# AxionAdapter.net
KiCad netlist of a schematic drawn in EAGLE
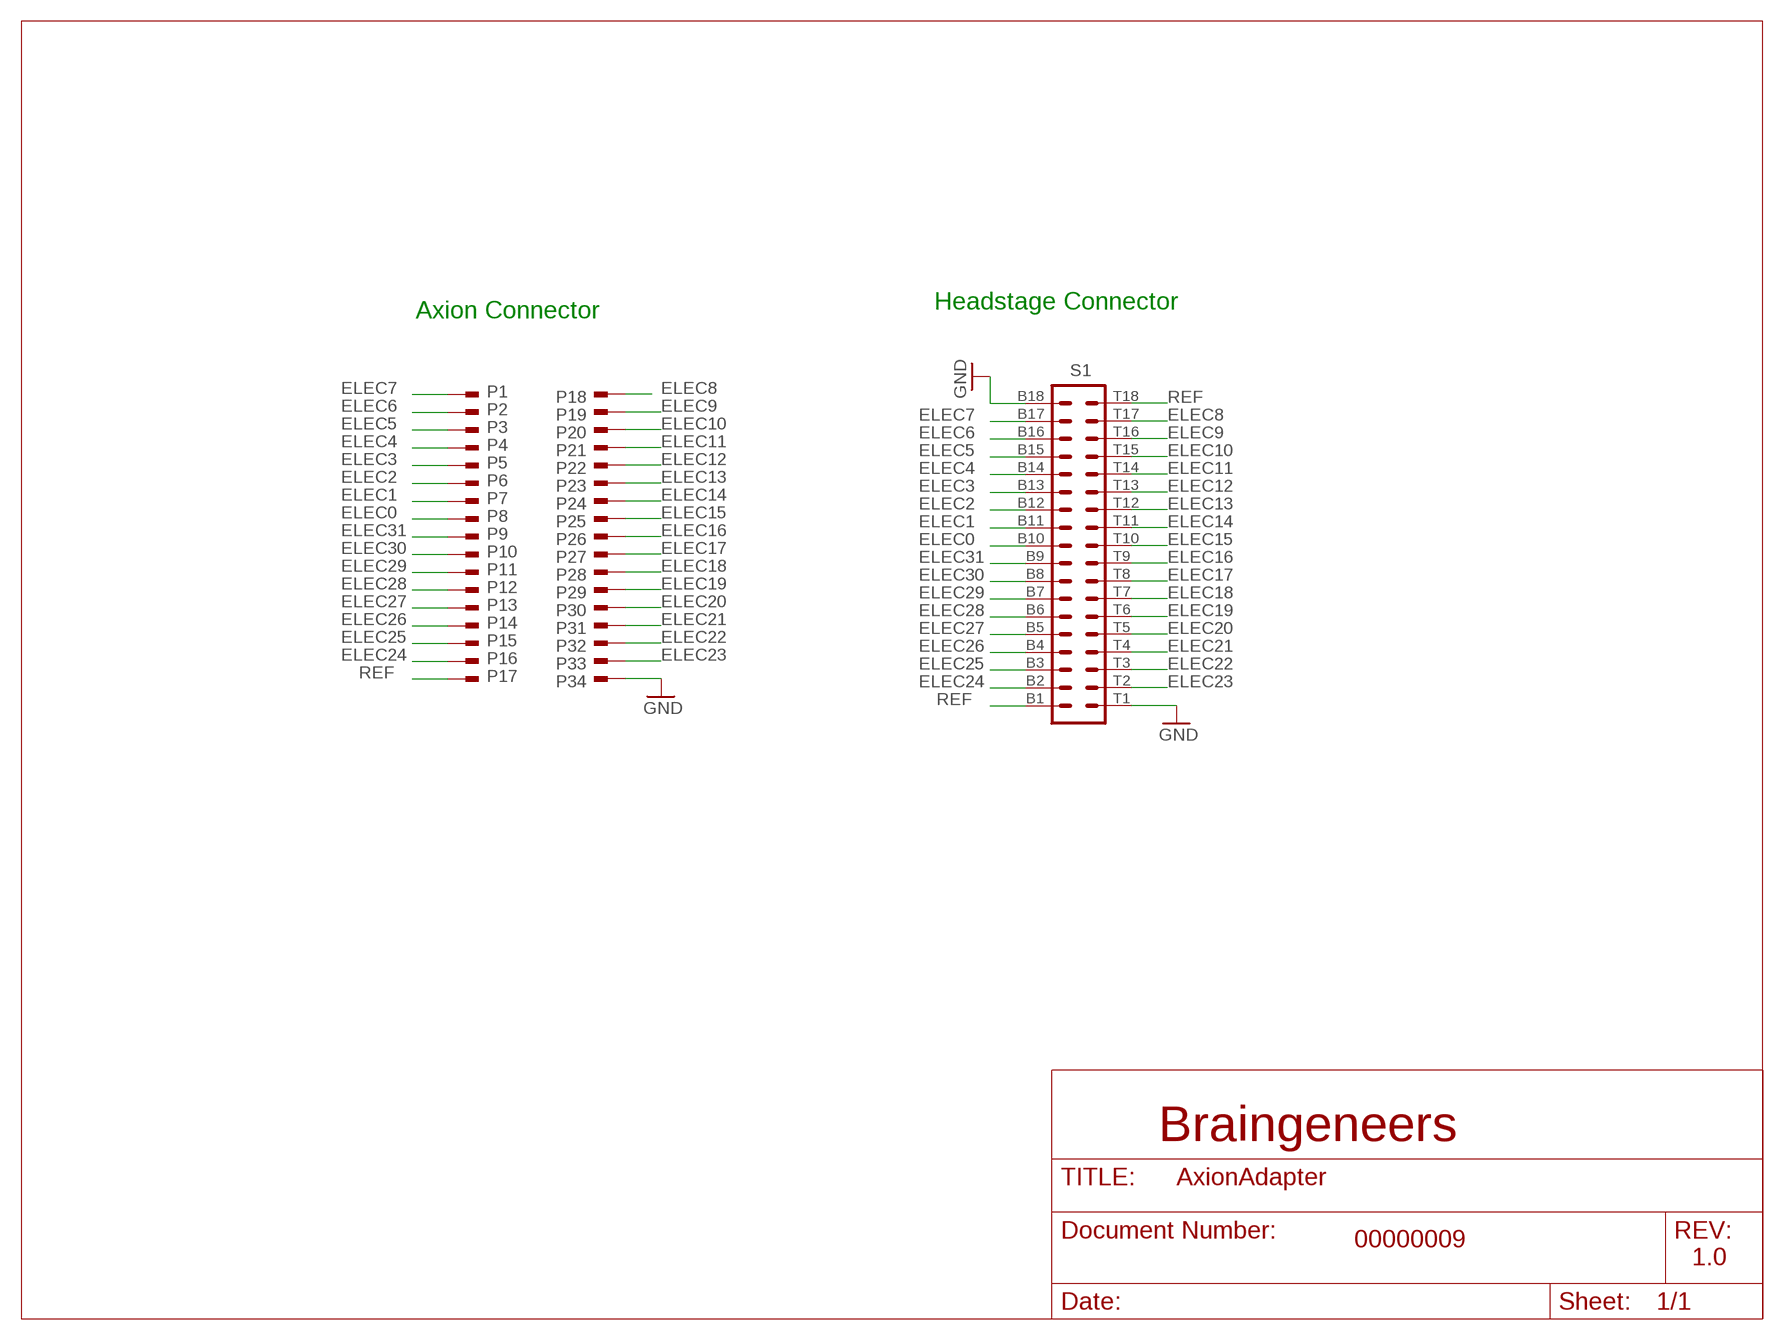
[diagram p0: schematic, sheet 1]

(export (version "E")
  (design (tool "Eeschema 10.0.6"))
  (components
    (comp (ref "P1")
      (value "2336713-2_TE")
      (footprint "eagle-import:2336713-2_TE")
      (libsource (lib "eagle-import") (part "2336713-2_TE"))
    )
    (comp (ref "P2")
      (value "2336713-2_TE")
      (footprint "eagle-import:2336713-2_TE")
      (libsource (lib "eagle-import") (part "2336713-2_TE"))
    )
    (comp (ref "P3")
      (value "2336713-2_TE")
      (footprint "eagle-import:2336713-2_TE")
      (libsource (lib "eagle-import") (part "2336713-2_TE"))
    )
    (comp (ref "P4")
      (value "2336713-2_TE")
      (footprint "eagle-import:2336713-2_TE")
      (libsource (lib "eagle-import") (part "2336713-2_TE"))
    )
    (comp (ref "P5")
      (value "2336713-2_TE")
      (footprint "eagle-import:2336713-2_TE")
      (libsource (lib "eagle-import") (part "2336713-2_TE"))
    )
    (comp (ref "P6")
      (value "2336713-2_TE")
      (footprint "eagle-import:2336713-2_TE")
      (libsource (lib "eagle-import") (part "2336713-2_TE"))
    )
    (comp (ref "P7")
      (value "2336713-2_TE")
      (footprint "eagle-import:2336713-2_TE")
      (libsource (lib "eagle-import") (part "2336713-2_TE"))
    )
    (comp (ref "P8")
      (value "2336713-2_TE")
      (footprint "eagle-import:2336713-2_TE")
      (libsource (lib "eagle-import") (part "2336713-2_TE"))
    )
    (comp (ref "P9")
      (value "2336713-2_TE")
      (footprint "eagle-import:2336713-2_TE")
      (libsource (lib "eagle-import") (part "2336713-2_TE"))
    )
    (comp (ref "P10")
      (value "2336713-2_TE")
      (footprint "eagle-import:2336713-2_TE")
      (libsource (lib "eagle-import") (part "2336713-2_TE"))
    )
    (comp (ref "P11")
      (value "2336713-2_TE")
      (footprint "eagle-import:2336713-2_TE")
      (libsource (lib "eagle-import") (part "2336713-2_TE"))
    )
    (comp (ref "P12")
      (value "2336713-2_TE")
      (footprint "eagle-import:2336713-2_TE")
      (libsource (lib "eagle-import") (part "2336713-2_TE"))
    )
    (comp (ref "P13")
      (value "2336713-2_TE")
      (footprint "eagle-import:2336713-2_TE")
      (libsource (lib "eagle-import") (part "2336713-2_TE"))
    )
    (comp (ref "P14")
      (value "2336713-2_TE")
      (footprint "eagle-import:2336713-2_TE")
      (libsource (lib "eagle-import") (part "2336713-2_TE"))
    )
    (comp (ref "P15")
      (value "2336713-2_TE")
      (footprint "eagle-import:2336713-2_TE")
      (libsource (lib "eagle-import") (part "2336713-2_TE"))
    )
    (comp (ref "P16")
      (value "2336713-2_TE")
      (footprint "eagle-import:2336713-2_TE")
      (libsource (lib "eagle-import") (part "2336713-2_TE"))
    )
    (comp (ref "P17")
      (value "2336713-2_TE")
      (footprint "eagle-import:2336713-2_TE")
      (libsource (lib "eagle-import") (part "2336713-2_TE"))
    )
    (comp (ref "P18")
      (value "2336713-2_TE")
      (footprint "eagle-import:2336713-2_TE")
      (libsource (lib "eagle-import") (part "2336713-2_TE"))
    )
    (comp (ref "P19")
      (value "2336713-2_TE")
      (footprint "eagle-import:2336713-2_TE")
      (libsource (lib "eagle-import") (part "2336713-2_TE"))
    )
    (comp (ref "P20")
      (value "2336713-2_TE")
      (footprint "eagle-import:2336713-2_TE")
      (libsource (lib "eagle-import") (part "2336713-2_TE"))
    )
    (comp (ref "P21")
      (value "2336713-2_TE")
      (footprint "eagle-import:2336713-2_TE")
      (libsource (lib "eagle-import") (part "2336713-2_TE"))
    )
    (comp (ref "P22")
      (value "2336713-2_TE")
      (footprint "eagle-import:2336713-2_TE")
      (libsource (lib "eagle-import") (part "2336713-2_TE"))
    )
    (comp (ref "P23")
      (value "2336713-2_TE")
      (footprint "eagle-import:2336713-2_TE")
      (libsource (lib "eagle-import") (part "2336713-2_TE"))
    )
    (comp (ref "P24")
      (value "2336713-2_TE")
      (footprint "eagle-import:2336713-2_TE")
      (libsource (lib "eagle-import") (part "2336713-2_TE"))
    )
    (comp (ref "P25")
      (value "2336713-2_TE")
      (footprint "eagle-import:2336713-2_TE")
      (libsource (lib "eagle-import") (part "2336713-2_TE"))
    )
    (comp (ref "P26")
      (value "2336713-2_TE")
      (footprint "eagle-import:2336713-2_TE")
      (libsource (lib "eagle-import") (part "2336713-2_TE"))
    )
    (comp (ref "P27")
      (value "2336713-2_TE")
      (footprint "eagle-import:2336713-2_TE")
      (libsource (lib "eagle-import") (part "2336713-2_TE"))
    )
    (comp (ref "P28")
      (value "2336713-2_TE")
      (footprint "eagle-import:2336713-2_TE")
      (libsource (lib "eagle-import") (part "2336713-2_TE"))
    )
    (comp (ref "P29")
      (value "2336713-2_TE")
      (footprint "eagle-import:2336713-2_TE")
      (libsource (lib "eagle-import") (part "2336713-2_TE"))
    )
    (comp (ref "P30")
      (value "2336713-2_TE")
      (footprint "eagle-import:2336713-2_TE")
      (libsource (lib "eagle-import") (part "2336713-2_TE"))
    )
    (comp (ref "P31")
      (value "2336713-2_TE")
      (footprint "eagle-import:2336713-2_TE")
      (libsource (lib "eagle-import") (part "2336713-2_TE"))
    )
    (comp (ref "P32")
      (value "2336713-2_TE")
      (footprint "eagle-import:2336713-2_TE")
      (libsource (lib "eagle-import") (part "2336713-2_TE"))
    )
    (comp (ref "P33")
      (value "2336713-2_TE")
      (footprint "eagle-import:2336713-2_TE")
      (libsource (lib "eagle-import") (part "2336713-2_TE"))
    )
    (comp (ref "P34")
      (value "2336713-2_TE")
      (footprint "eagle-import:2336713-2_TE")
      (libsource (lib "eagle-import") (part "2336713-2_TE"))
    )
    (comp (ref "S1")
      (value "OMNETICS_A79024")
      (footprint "eagle-import:OMNETICS_A79024")
      (libsource (lib "eagle-import") (part "OMNETICS_A79024"))
    )
  )
  (nets
    (net (code "1") (name "/ELEC0") (class "Default")
      (node (ref "P8") (pin "P$1") (pinfunction "1_P$1") (pintype "passive"))
      (node (ref "P8") (pin "P$2") (pinfunction "1_P$2") (pintype "passive"))
      (node (ref "S1") (pin "B10") (pinfunction "B10_B10") (pintype "passive"))
    )
    (net (code "2") (name "/ELEC1") (class "Default")
      (node (ref "P7") (pin "P$1") (pinfunction "1_P$1") (pintype "passive"))
      (node (ref "P7") (pin "P$2") (pinfunction "1_P$2") (pintype "passive"))
      (node (ref "S1") (pin "B11") (pinfunction "B11_B11") (pintype "passive"))
    )
    (net (code "3") (name "/ELEC2") (class "Default")
      (node (ref "P6") (pin "P$1") (pinfunction "1_P$1") (pintype "passive"))
      (node (ref "P6") (pin "P$2") (pinfunction "1_P$2") (pintype "passive"))
      (node (ref "S1") (pin "B12") (pinfunction "B12_B12") (pintype "passive"))
    )
    (net (code "4") (name "/ELEC3") (class "Default")
      (node (ref "P5") (pin "P$1") (pinfunction "1_P$1") (pintype "passive"))
      (node (ref "P5") (pin "P$2") (pinfunction "1_P$2") (pintype "passive"))
      (node (ref "S1") (pin "B13") (pinfunction "B13_B13") (pintype "passive"))
    )
    (net (code "5") (name "/ELEC4") (class "Default")
      (node (ref "P4") (pin "P$1") (pinfunction "1_P$1") (pintype "passive"))
      (node (ref "P4") (pin "P$2") (pinfunction "1_P$2") (pintype "passive"))
      (node (ref "S1") (pin "B14") (pinfunction "B14_B14") (pintype "passive"))
    )
    (net (code "6") (name "/ELEC5") (class "Default")
      (node (ref "P3") (pin "P$1") (pinfunction "1_P$1") (pintype "passive"))
      (node (ref "P3") (pin "P$2") (pinfunction "1_P$2") (pintype "passive"))
      (node (ref "S1") (pin "B15") (pinfunction "B15_B15") (pintype "passive"))
    )
    (net (code "7") (name "/ELEC6") (class "Default")
      (node (ref "P2") (pin "P$1") (pinfunction "1_P$1") (pintype "passive"))
      (node (ref "P2") (pin "P$2") (pinfunction "1_P$2") (pintype "passive"))
      (node (ref "S1") (pin "B16") (pinfunction "B16_B16") (pintype "passive"))
    )
    (net (code "8") (name "/ELEC7") (class "Default")
      (node (ref "P1") (pin "P$1") (pinfunction "1_P$1") (pintype "passive"))
      (node (ref "P1") (pin "P$2") (pinfunction "1_P$2") (pintype "passive"))
      (node (ref "S1") (pin "B17") (pinfunction "B17_B17") (pintype "passive"))
    )
    (net (code "9") (name "/ELEC8") (class "Default")
      (node (ref "P18") (pin "P$1") (pinfunction "1_P$1") (pintype "passive"))
      (node (ref "P18") (pin "P$2") (pinfunction "1_P$2") (pintype "passive"))
      (node (ref "S1") (pin "T17") (pinfunction "T17_T17") (pintype "passive"))
    )
    (net (code "10") (name "/ELEC9") (class "Default")
      (node (ref "P19") (pin "P$1") (pinfunction "1_P$1") (pintype "passive"))
      (node (ref "P19") (pin "P$2") (pinfunction "1_P$2") (pintype "passive"))
      (node (ref "S1") (pin "T16") (pinfunction "T16_T16") (pintype "passive"))
    )
    (net (code "11") (name "/ELEC10") (class "Default")
      (node (ref "P20") (pin "P$1") (pinfunction "1_P$1") (pintype "passive"))
      (node (ref "P20") (pin "P$2") (pinfunction "1_P$2") (pintype "passive"))
      (node (ref "S1") (pin "T15") (pinfunction "T15_T15") (pintype "passive"))
    )
    (net (code "12") (name "/ELEC11") (class "Default")
      (node (ref "P21") (pin "P$1") (pinfunction "1_P$1") (pintype "passive"))
      (node (ref "P21") (pin "P$2") (pinfunction "1_P$2") (pintype "passive"))
      (node (ref "S1") (pin "T14") (pinfunction "T14_T14") (pintype "passive"))
    )
    (net (code "13") (name "/ELEC12") (class "Default")
      (node (ref "P22") (pin "P$1") (pinfunction "1_P$1") (pintype "passive"))
      (node (ref "P22") (pin "P$2") (pinfunction "1_P$2") (pintype "passive"))
      (node (ref "S1") (pin "T13") (pinfunction "T13_T13") (pintype "passive"))
    )
    (net (code "14") (name "/ELEC13") (class "Default")
      (node (ref "P23") (pin "P$1") (pinfunction "1_P$1") (pintype "passive"))
      (node (ref "P23") (pin "P$2") (pinfunction "1_P$2") (pintype "passive"))
      (node (ref "S1") (pin "T12") (pinfunction "T12_T12") (pintype "passive"))
    )
    (net (code "15") (name "/ELEC14") (class "Default")
      (node (ref "P24") (pin "P$1") (pinfunction "1_P$1") (pintype "passive"))
      (node (ref "P24") (pin "P$2") (pinfunction "1_P$2") (pintype "passive"))
      (node (ref "S1") (pin "T11") (pinfunction "T11_T11") (pintype "passive"))
    )
    (net (code "16") (name "/ELEC15") (class "Default")
      (node (ref "P25") (pin "P$1") (pinfunction "1_P$1") (pintype "passive"))
      (node (ref "P25") (pin "P$2") (pinfunction "1_P$2") (pintype "passive"))
      (node (ref "S1") (pin "T10") (pinfunction "T10_T10") (pintype "passive"))
    )
    (net (code "17") (name "/ELEC16") (class "Default")
      (node (ref "P26") (pin "P$1") (pinfunction "1_P$1") (pintype "passive"))
      (node (ref "P26") (pin "P$2") (pinfunction "1_P$2") (pintype "passive"))
      (node (ref "S1") (pin "T9") (pinfunction "T9_T9") (pintype "passive"))
    )
    (net (code "18") (name "/ELEC17") (class "Default")
      (node (ref "P27") (pin "P$1") (pinfunction "1_P$1") (pintype "passive"))
      (node (ref "P27") (pin "P$2") (pinfunction "1_P$2") (pintype "passive"))
      (node (ref "S1") (pin "T8") (pinfunction "T8_T8") (pintype "passive"))
    )
    (net (code "19") (name "/ELEC18") (class "Default")
      (node (ref "P28") (pin "P$1") (pinfunction "1_P$1") (pintype "passive"))
      (node (ref "P28") (pin "P$2") (pinfunction "1_P$2") (pintype "passive"))
      (node (ref "S1") (pin "T7") (pinfunction "T7_T7") (pintype "passive"))
    )
    (net (code "20") (name "/ELEC19") (class "Default")
      (node (ref "P29") (pin "P$1") (pinfunction "1_P$1") (pintype "passive"))
      (node (ref "P29") (pin "P$2") (pinfunction "1_P$2") (pintype "passive"))
      (node (ref "S1") (pin "T6") (pinfunction "T6_T6") (pintype "passive"))
    )
    (net (code "21") (name "/ELEC20") (class "Default")
      (node (ref "P30") (pin "P$1") (pinfunction "1_P$1") (pintype "passive"))
      (node (ref "P30") (pin "P$2") (pinfunction "1_P$2") (pintype "passive"))
      (node (ref "S1") (pin "T5") (pinfunction "T5_T5") (pintype "passive"))
    )
    (net (code "22") (name "/ELEC21") (class "Default")
      (node (ref "P31") (pin "P$1") (pinfunction "1_P$1") (pintype "passive"))
      (node (ref "P31") (pin "P$2") (pinfunction "1_P$2") (pintype "passive"))
      (node (ref "S1") (pin "T4") (pinfunction "T4_T4") (pintype "passive"))
    )
    (net (code "23") (name "/ELEC22") (class "Default")
      (node (ref "P32") (pin "P$1") (pinfunction "1_P$1") (pintype "passive"))
      (node (ref "P32") (pin "P$2") (pinfunction "1_P$2") (pintype "passive"))
      (node (ref "S1") (pin "T3") (pinfunction "T3_T3") (pintype "passive"))
    )
    (net (code "24") (name "/ELEC23") (class "Default")
      (node (ref "P33") (pin "P$1") (pinfunction "1_P$1") (pintype "passive"))
      (node (ref "P33") (pin "P$2") (pinfunction "1_P$2") (pintype "passive"))
      (node (ref "S1") (pin "T2") (pinfunction "T2_T2") (pintype "passive"))
    )
    (net (code "25") (name "/ELEC24") (class "Default")
      (node (ref "P16") (pin "P$1") (pinfunction "1_P$1") (pintype "passive"))
      (node (ref "P16") (pin "P$2") (pinfunction "1_P$2") (pintype "passive"))
      (node (ref "S1") (pin "B2") (pinfunction "B2_B2") (pintype "passive"))
    )
    (net (code "26") (name "/ELEC25") (class "Default")
      (node (ref "P15") (pin "P$1") (pinfunction "1_P$1") (pintype "passive"))
      (node (ref "P15") (pin "P$2") (pinfunction "1_P$2") (pintype "passive"))
      (node (ref "S1") (pin "B3") (pinfunction "B3_B3") (pintype "passive"))
    )
    (net (code "27") (name "/ELEC26") (class "Default")
      (node (ref "P14") (pin "P$1") (pinfunction "1_P$1") (pintype "passive"))
      (node (ref "P14") (pin "P$2") (pinfunction "1_P$2") (pintype "passive"))
      (node (ref "S1") (pin "B4") (pinfunction "B4_B4") (pintype "passive"))
    )
    (net (code "28") (name "/ELEC27") (class "Default")
      (node (ref "P13") (pin "P$1") (pinfunction "1_P$1") (pintype "passive"))
      (node (ref "P13") (pin "P$2") (pinfunction "1_P$2") (pintype "passive"))
      (node (ref "S1") (pin "B5") (pinfunction "B5_B5") (pintype "passive"))
    )
    (net (code "29") (name "/ELEC28") (class "Default")
      (node (ref "P12") (pin "P$1") (pinfunction "1_P$1") (pintype "passive"))
      (node (ref "P12") (pin "P$2") (pinfunction "1_P$2") (pintype "passive"))
      (node (ref "S1") (pin "B6") (pinfunction "B6_B6") (pintype "passive"))
    )
    (net (code "30") (name "/ELEC29") (class "Default")
      (node (ref "P11") (pin "P$1") (pinfunction "1_P$1") (pintype "passive"))
      (node (ref "P11") (pin "P$2") (pinfunction "1_P$2") (pintype "passive"))
      (node (ref "S1") (pin "B7") (pinfunction "B7_B7") (pintype "passive"))
    )
    (net (code "31") (name "/ELEC30") (class "Default")
      (node (ref "P10") (pin "P$1") (pinfunction "1_P$1") (pintype "passive"))
      (node (ref "P10") (pin "P$2") (pinfunction "1_P$2") (pintype "passive"))
      (node (ref "S1") (pin "B8") (pinfunction "B8_B8") (pintype "passive"))
    )
    (net (code "32") (name "/ELEC31") (class "Default")
      (node (ref "P9") (pin "P$1") (pinfunction "1_P$1") (pintype "passive"))
      (node (ref "P9") (pin "P$2") (pinfunction "1_P$2") (pintype "passive"))
      (node (ref "S1") (pin "B9") (pinfunction "B9_B9") (pintype "passive"))
    )
    (net (code "33") (name "/REF") (class "Default")
      (node (ref "P17") (pin "P$1") (pinfunction "1_P$1") (pintype "passive"))
      (node (ref "P17") (pin "P$2") (pinfunction "1_P$2") (pintype "passive"))
      (node (ref "S1") (pin "B1") (pinfunction "B1_B1") (pintype "passive"))
      (node (ref "S1") (pin "T18") (pinfunction "T18_T18") (pintype "passive"))
    )
    (net (code "34") (name "GND") (class "Default")
      (node (ref "P34") (pin "P$1") (pinfunction "1_P$1") (pintype "passive"))
      (node (ref "P34") (pin "P$2") (pinfunction "1_P$2") (pintype "passive"))
      (node (ref "S1") (pin "B18") (pinfunction "B18_B18") (pintype "passive"))
      (node (ref "S1") (pin "T1") (pinfunction "T1_T1") (pintype "passive"))
    )
  )
)
